# SC70-6-minimal.net
KiCad netlist of a schematic drawn in EAGLE
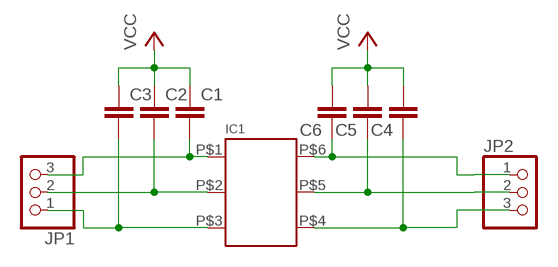
[diagram p0: schematic, sheet 1]

(export (version "E")
  (design (tool "Eeschema 10.0.6"))
  (components
    (comp (ref "C1")
      (value "C-EUC0603")
      (footprint "eagle-import:C0603")
      (libsource (lib "eagle-import") (part "C-EUC0603"))
    )
    (comp (ref "C2")
      (value "C-EUC0603")
      (footprint "eagle-import:C0603")
      (libsource (lib "eagle-import") (part "C-EUC0603"))
    )
    (comp (ref "C3")
      (value "C-EUC0603")
      (footprint "eagle-import:C0603")
      (libsource (lib "eagle-import") (part "C-EUC0603"))
    )
    (comp (ref "C4")
      (value "C-EUC0603")
      (footprint "eagle-import:C0603")
      (libsource (lib "eagle-import") (part "C-EUC0603"))
    )
    (comp (ref "C5")
      (value "C-EUC0603")
      (footprint "eagle-import:C0603")
      (libsource (lib "eagle-import") (part "C-EUC0603"))
    )
    (comp (ref "C6")
      (value "C-EUC0603")
      (footprint "eagle-import:C0603")
      (libsource (lib "eagle-import") (part "C-EUC0603"))
    )
    (comp (ref "IC1")
      (value "FOOTPRINT-6-PINSC70")
      (footprint "eagle-import:SC-70_6")
      (libsource (lib "eagle-import") (part "FOOTPRINT-6-PINSC70"))
    )
    (comp (ref "JP1")
      (value "PINHD-1X3")
      (footprint "eagle-import:1X03")
      (libsource (lib "eagle-import") (part "PINHD-1X3"))
    )
    (comp (ref "JP2")
      (value "PINHD-1X3")
      (footprint "eagle-import:1X03")
      (libsource (lib "eagle-import") (part "PINHD-1X3"))
    )
  )
  (nets
    (net (code "1") (name "Net-(IC1-1)") (class "Default")
      (node (ref "C1") (pin "2") (pinfunction "2_2") (pintype "passive"))
      (node (ref "IC1") (pin "P$1") (pinfunction "1_P$1") (pintype "bidirectional"))
      (node (ref "JP1") (pin "3") (pinfunction "3_3") (pintype "passive"))
    )
    (net (code "2") (name "Net-(IC1-2)") (class "Default")
      (node (ref "C2") (pin "2") (pinfunction "2_2") (pintype "passive"))
      (node (ref "IC1") (pin "P$2") (pinfunction "2_P$2") (pintype "bidirectional"))
      (node (ref "JP1") (pin "2") (pinfunction "2_2") (pintype "passive"))
    )
    (net (code "3") (name "Net-(IC1-3)") (class "Default")
      (node (ref "C3") (pin "2") (pinfunction "2_2") (pintype "passive"))
      (node (ref "IC1") (pin "P$3") (pinfunction "3_P$3") (pintype "bidirectional"))
      (node (ref "JP1") (pin "1") (pinfunction "1_1") (pintype "passive"))
    )
    (net (code "4") (name "Net-(IC1-4)") (class "Default")
      (node (ref "C4") (pin "1") (pinfunction "1_1") (pintype "passive"))
      (node (ref "IC1") (pin "P$4") (pinfunction "4_P$4") (pintype "bidirectional"))
      (node (ref "JP2") (pin "3") (pinfunction "3_3") (pintype "passive"))
    )
    (net (code "5") (name "Net-(IC1-5)") (class "Default")
      (node (ref "C5") (pin "1") (pinfunction "1_1") (pintype "passive"))
      (node (ref "IC1") (pin "P$5") (pinfunction "5_P$5") (pintype "bidirectional"))
      (node (ref "JP2") (pin "2") (pinfunction "2_2") (pintype "passive"))
    )
    (net (code "6") (name "Net-(IC1-6)") (class "Default")
      (node (ref "C6") (pin "1") (pinfunction "1_1") (pintype "passive"))
      (node (ref "IC1") (pin "P$6") (pinfunction "6_P$6") (pintype "bidirectional"))
      (node (ref "JP2") (pin "1") (pinfunction "1_1") (pintype "passive"))
    )
    (net (code "7") (name "VCC") (class "Default")
      (node (ref "C1") (pin "1") (pinfunction "1_1") (pintype "passive"))
      (node (ref "C2") (pin "1") (pinfunction "1_1") (pintype "passive"))
      (node (ref "C3") (pin "1") (pinfunction "1_1") (pintype "passive"))
      (node (ref "C4") (pin "2") (pinfunction "2_2") (pintype "passive"))
      (node (ref "C5") (pin "2") (pinfunction "2_2") (pintype "passive"))
      (node (ref "C6") (pin "2") (pinfunction "2_2") (pintype "passive"))
    )
  )
)
